# AbraSchematicVer5_SchDoc.net
KiCad netlist of a schematic drawn in Altium Designer
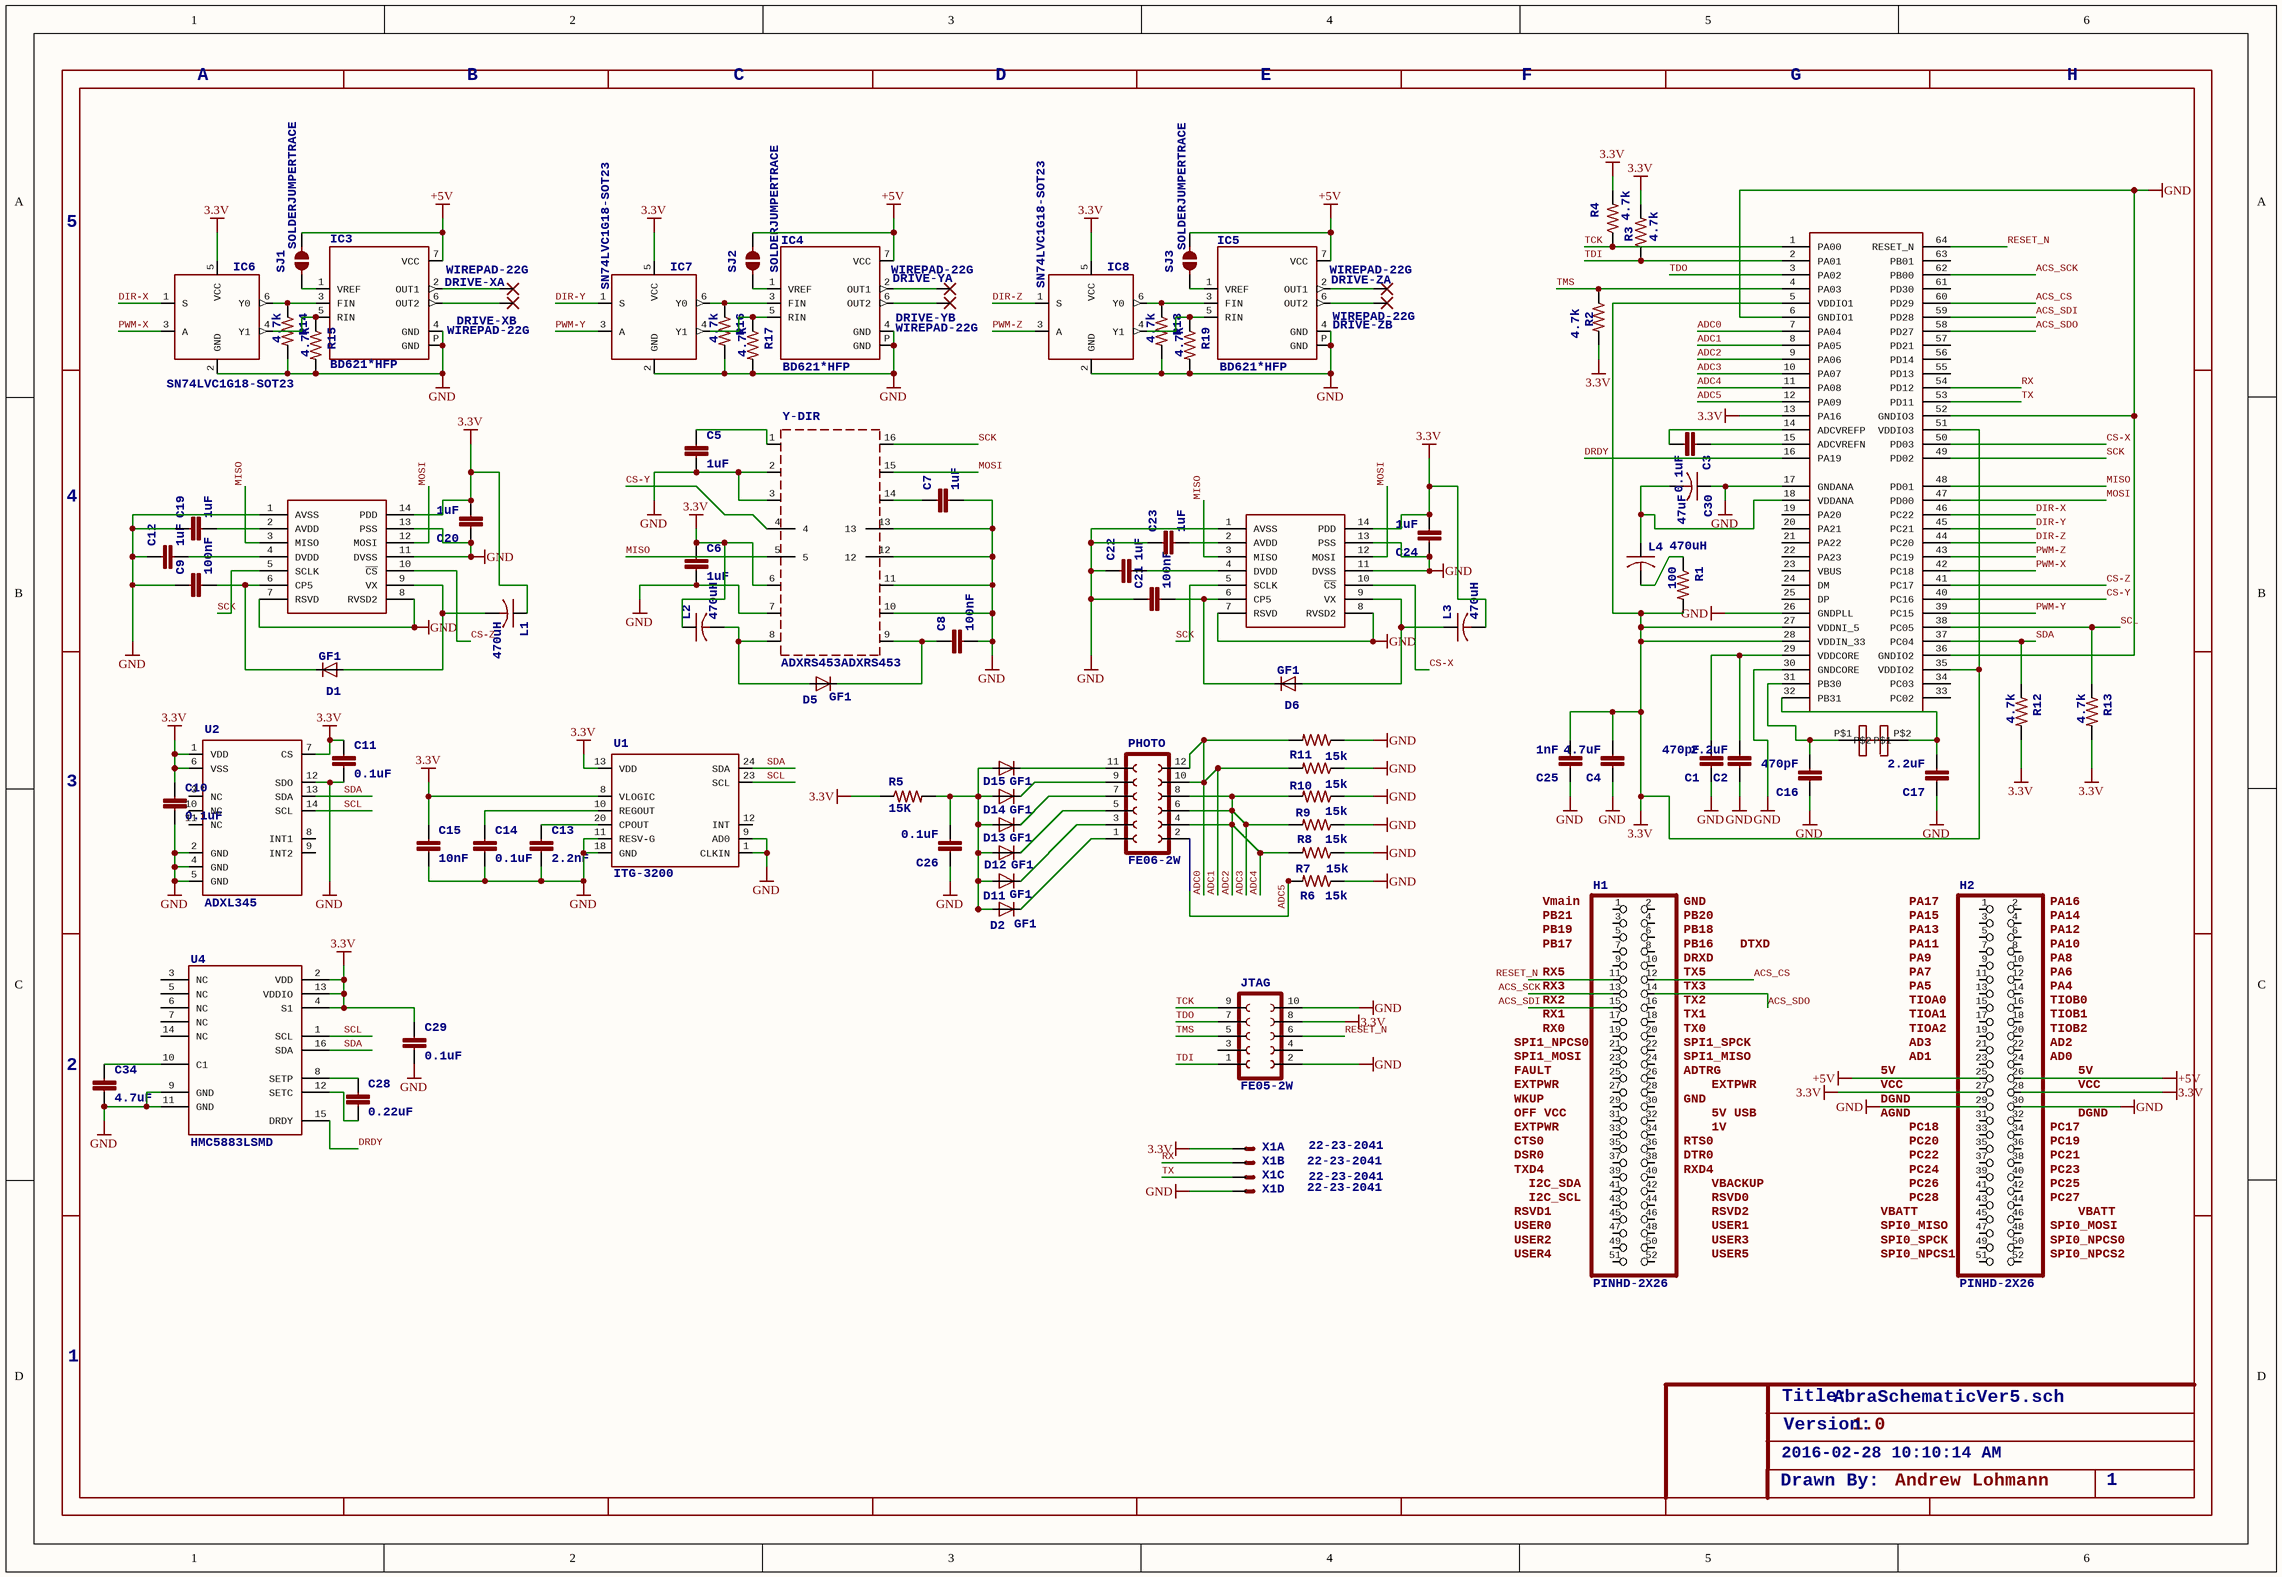
[diagram p0: AbraSchematicVer5.SchDoc.SchDoc]

(export (version "E")
  (design (tool "Eeschema 10.0.6"))
  (components
    (comp (ref "AXDRS453-LCC_X-DIR")
      (value "ADXRS453-LCC")
      (footprint "ADX-VERT")
      (libsource (lib "AndrewLib") (part "ADXRS453-LCC"))
    )
    (comp (ref "AXDRS453-LCC_Z-DIR")
      (value "ADXRS453-LCC")
      (footprint "ADX-VERT")
      (libsource (lib "AndrewLib") (part "ADXRS453-LCC"))
    )
    (comp (ref "C1")
      (value "470pF")
      (footprint "0603-CAP")
      (description "<b>Capacitor</b>\nStandard SMT, and 0.1\", and 0.2\" leaded ceramic capacitors")
      (libsource (lib "") (part "CAPACITOR-0603_2"))
    )
    (comp (ref "C2")
      (value "2.2uF")
      (footprint "0603-CAP")
      (description "<b>Capacitor</b>\nStandard SMT, and 0.1\", and 0.2\" leaded ceramic capacitors")
      (libsource (lib "") (part "CAPACITOR-0603_2"))
    )
    (comp (ref "C3")
      (value "0.1uF")
      (footprint "0603-CAP")
      (description "<b>Capacitor</b>\nStandard SMT, and 0.1\", and 0.2\" leaded ceramic capacitors")
      (libsource (lib "") (part "CAPACITOR-0603_3"))
    )
    (comp (ref "C4")
      (value "4.7uF")
      (footprint "0603-CAP")
      (description "<b>Capacitor</b>\nStandard SMT, and 0.1\", and 0.2\" leaded ceramic capacitors")
      (libsource (lib "") (part "CAPACITOR-0603_2"))
    )
    (comp (ref "C5")
      (value "1uF")
      (footprint "0603-CAP")
      (description "<b>Capacitor</b>\nStandard SMT, and 0.1\", and 0.2\" leaded ceramic capacitors")
      (libsource (lib "") (part "CAPACITOR-0603_1"))
    )
    (comp (ref "C6")
      (value "1uF")
      (footprint "0603-CAP")
      (description "<b>Capacitor</b>\nStandard SMT, and 0.1\", and 0.2\" leaded ceramic capacitors")
      (libsource (lib "") (part "CAPACITOR-0603_1"))
    )
    (comp (ref "C7")
      (value "1uF")
      (footprint "0603-CAP")
      (description "<b>Capacitor</b>\nStandard SMT, and 0.1\", and 0.2\" leaded ceramic capacitors")
      (libsource (lib "urover") (part "CAPACITOR-0603"))
    )
    (comp (ref "C8")
      (value "100nF")
      (footprint "0603-CAP")
      (description "<b>Capacitor</b>\nStandard SMT, and 0.1\", and 0.2\" leaded ceramic capacitors")
      (libsource (lib "urover") (part "CAPACITOR-0603"))
    )
    (comp (ref "C9")
      (value "100nF")
      (footprint "0603-CAP")
      (description "<b>Capacitor</b>\nStandard SMT, and 0.1\", and 0.2\" leaded ceramic capacitors")
      (libsource (lib "urover") (part "CAPACITOR-0603"))
    )
    (comp (ref "C10")
      (value "0.1uF")
      (footprint "0603-CAP")
      (description "<b>Capacitor</b>\nStandard SMT, and 0.1\", and 0.2\" leaded ceramic capacitors")
      (libsource (lib "") (part "CAPACITOR-0603_1"))
    )
    (comp (ref "C11")
      (value "0.1uF")
      (footprint "0603-CAP")
      (description "<b>Capacitor</b>\nStandard SMT, and 0.1\", and 0.2\" leaded ceramic capacitors")
      (libsource (lib "") (part "CAPACITOR-0603_1"))
    )
    (comp (ref "C12")
      (value "1uF")
      (footprint "0603-CAP")
      (description "<b>Capacitor</b>\nStandard SMT, and 0.1\", and 0.2\" leaded ceramic capacitors")
      (libsource (lib "urover") (part "CAPACITOR-0603"))
    )
    (comp (ref "C13")
      (value "2.2nF")
      (footprint "0603-CAP")
      (description "<b>Capacitor</b>\nStandard SMT, and 0.1\", and 0.2\" leaded ceramic capacitors")
      (libsource (lib "") (part "CAPACITOR-0603_1"))
    )
    (comp (ref "C14")
      (value "0.1uF")
      (footprint "0603-CAP")
      (description "<b>Capacitor</b>\nStandard SMT, and 0.1\", and 0.2\" leaded ceramic capacitors")
      (libsource (lib "") (part "CAPACITOR-0603_1"))
    )
    (comp (ref "C15")
      (value "10nF")
      (footprint "0603-CAP")
      (description "<b>Capacitor</b>\nStandard SMT, and 0.1\", and 0.2\" leaded ceramic capacitors")
      (libsource (lib "") (part "CAPACITOR-0603_1"))
    )
    (comp (ref "C16")
      (value "470pF")
      (footprint "0603-CAP")
      (description "<b>Capacitor</b>\nStandard SMT, and 0.1\", and 0.2\" leaded ceramic capacitors")
      (libsource (lib "") (part "CAPACITOR-0603_2"))
    )
    (comp (ref "C17")
      (value "2.2uF")
      (footprint "0603-CAP")
      (description "<b>Capacitor</b>\nStandard SMT, and 0.1\", and 0.2\" leaded ceramic capacitors")
      (libsource (lib "") (part "CAPACITOR-0603_2"))
    )
    (comp (ref "C19")
      (value "1uF")
      (footprint "0603-CAP")
      (description "<b>Capacitor</b>\nStandard SMT, and 0.1\", and 0.2\" leaded ceramic capacitors")
      (libsource (lib "urover") (part "CAPACITOR-0603"))
    )
    (comp (ref "C20")
      (value "1uF")
      (footprint "0603-CAP")
      (description "<b>Capacitor</b>\nStandard SMT, and 0.1\", and 0.2\" leaded ceramic capacitors")
      (libsource (lib "") (part "CAPACITOR-0603_2"))
    )
    (comp (ref "C21")
      (value "100nF")
      (footprint "0603-CAP")
      (description "<b>Capacitor</b>\nStandard SMT, and 0.1\", and 0.2\" leaded ceramic capacitors")
      (libsource (lib "urover") (part "CAPACITOR-0603"))
    )
    (comp (ref "C22")
      (value "1uF")
      (footprint "0603-CAP")
      (description "<b>Capacitor</b>\nStandard SMT, and 0.1\", and 0.2\" leaded ceramic capacitors")
      (libsource (lib "urover") (part "CAPACITOR-0603"))
    )
    (comp (ref "C23")
      (value "1uF")
      (footprint "0603-CAP")
      (description "<b>Capacitor</b>\nStandard SMT, and 0.1\", and 0.2\" leaded ceramic capacitors")
      (libsource (lib "urover") (part "CAPACITOR-0603"))
    )
    (comp (ref "C24")
      (value "1uF")
      (footprint "0603-CAP")
      (description "<b>Capacitor</b>\nStandard SMT, and 0.1\", and 0.2\" leaded ceramic capacitors")
      (libsource (lib "") (part "CAPACITOR-0603_2"))
    )
    (comp (ref "C25")
      (value "1nF")
      (footprint "0603-CAP")
      (description "<b>Capacitor</b>\nStandard SMT, and 0.1\", and 0.2\" leaded ceramic capacitors")
      (libsource (lib "") (part "CAPACITOR-0603_2"))
    )
    (comp (ref "C26")
      (value "0.1uF")
      (footprint "0603-CAP")
      (description "<b>Capacitor</b>\nStandard SMT, and 0.1\", and 0.2\" leaded ceramic capacitors")
      (libsource (lib "") (part "CAPACITOR-0603_2"))
    )
    (comp (ref "C28")
      (value "0.22uF")
      (footprint "0603-CAP")
      (description "<b>Capacitor</b>\nStandard SMT, and 0.1\", and 0.2\" leaded ceramic capacitors")
      (libsource (lib "") (part "CAPACITOR-0603_1"))
    )
    (comp (ref "C29")
      (value "0.1uF")
      (footprint "0603-CAP")
      (description "<b>Capacitor</b>\nStandard SMT, and 0.1\", and 0.2\" leaded ceramic capacitors")
      (libsource (lib "") (part "CAPACITOR-0603_1"))
    )
    (comp (ref "C30")
      (value "47uF")
      (footprint "C1210K")
      (description "<B>CAPACITOR</B>, American symbol")
      (libsource (lib "rcl") (part "C-USC1210K"))
    )
    (comp (ref "C34")
      (value "4.7uF")
      (footprint "0603-CAP")
      (description "<b>Capacitor</b>\nStandard SMT, and 0.1\", and 0.2\" leaded ceramic capacitors")
      (libsource (lib "") (part "CAPACITOR-0603_1"))
    )
    (comp (ref "CRYSTAL")
      (value "CRYSTAL-CAP")
      (footprint "CSM-3X_SMD")
      (libsource (lib "AndrewLib") (part "CRYSTAL-CAP"))
    )
    (comp (ref "D1")
      (value "GF1")
      (footprint "SMA-DO214AC")
      (description "<B>DIODE</B>")
      (libsource (lib "diode") (part "GF1"))
    )
    (comp (ref "D2")
      (value "GF1")
      (footprint "SMA-DO214AC")
      (description "<B>DIODE</B>")
      (libsource (lib "diode") (part "GF1"))
    )
    (comp (ref "D5")
      (value "GF1")
      (footprint "SMA-DO214AC")
      (description "<B>DIODE</B>")
      (libsource (lib "diode") (part "GF1"))
    )
    (comp (ref "D6")
      (value "GF1")
      (footprint "SMA-DO214AC")
      (description "<B>DIODE</B>")
      (libsource (lib "diode") (part "GF1"))
    )
    (comp (ref "D11")
      (value "GF1")
      (footprint "SMA-DO214AC")
      (description "<B>DIODE</B>")
      (libsource (lib "diode") (part "GF1"))
    )
    (comp (ref "D12")
      (value "GF1")
      (footprint "SMA-DO214AC")
      (description "<B>DIODE</B>")
      (libsource (lib "diode") (part "GF1"))
    )
    (comp (ref "D13")
      (value "GF1")
      (footprint "SMA-DO214AC")
      (description "<B>DIODE</B>")
      (libsource (lib "diode") (part "GF1"))
    )
    (comp (ref "D14")
      (value "GF1")
      (footprint "SMA-DO214AC")
      (description "<B>DIODE</B>")
      (libsource (lib "diode") (part "GF1"))
    )
    (comp (ref "D15")
      (value "GF1")
      (footprint "SMA-DO214AC")
      (description "<B>DIODE</B>")
      (libsource (lib "diode") (part "GF1"))
    )
    (comp (ref "DRIVE-XA")
      (value "WIREPAD-22G")
      (footprint "PAD-22G")
      (description "<b>THROUGH-HOLE PAD</b>")
      (libsource (lib "urover") (part "WIREPAD-22G"))
    )
    (comp (ref "DRIVE-XB")
      (value "WIREPAD-22G")
      (footprint "PAD-22G")
      (description "<b>THROUGH-HOLE PAD</b>")
      (libsource (lib "urover") (part "WIREPAD-22G"))
    )
    (comp (ref "DRIVE-YA")
      (value "WIREPAD-22G")
      (footprint "PAD-22G")
      (description "<b>THROUGH-HOLE PAD</b>")
      (libsource (lib "urover") (part "WIREPAD-22G"))
    )
    (comp (ref "DRIVE-YB")
      (value "WIREPAD-22G")
      (footprint "PAD-22G")
      (description "<b>THROUGH-HOLE PAD</b>")
      (libsource (lib "urover") (part "WIREPAD-22G"))
    )
    (comp (ref "DRIVE-ZA")
      (value "WIREPAD-22G")
      (footprint "PAD-22G")
      (description "<b>THROUGH-HOLE PAD</b>")
      (libsource (lib "urover") (part "WIREPAD-22G"))
    )
    (comp (ref "DRIVE-ZB")
      (value "WIREPAD-22G")
      (footprint "PAD-22G")
      (description "<b>THROUGH-HOLE PAD</b>")
      (libsource (lib "urover") (part "WIREPAD-22G"))
    )
    (comp (ref "H1")
      (value "PINHD-2X26")
      (footprint "HEADER-2X26")
      (description "<b>PIN HEADER</b>")
      (libsource (lib "urover") (part "PINHD-2X26"))
    )
    (comp (ref "H2")
      (value "PINHD-2X26")
      (footprint "HEADER-2X26")
      (description "<b>PIN HEADER</b>")
      (libsource (lib "urover") (part "PINHD-2X26"))
    )
    (comp (ref "IC3")
      (value "BD621*HFP")
      (footprint "HRP7")
      (fields (field (name "MPN") "BD6232HFP-TR"))
      (libsource (lib "urover") (part "BD621*HFP"))
    )
    (comp (ref "IC4")
      (value "BD621*HFP")
      (footprint "HRP7")
      (fields (field (name "MPN") "BD6232HFP-TR"))
      (libsource (lib "urover") (part "BD621*HFP"))
    )
    (comp (ref "IC5")
      (value "BD621*HFP")
      (footprint "HRP7")
      (fields (field (name "MPN") "BD6232HFP-TR"))
      (libsource (lib "urover") (part "BD621*HFP"))
    )
    (comp (ref "IC6")
      (value "SN74LVC1G18-SOT23")
      (footprint "SOT23-6")
      (libsource (lib "urover") (part "SN74LVC1G18-SOT23"))
    )
    (comp (ref "IC7")
      (value "SN74LVC1G18-SOT23")
      (footprint "SOT23-6")
      (libsource (lib "urover") (part "SN74LVC1G18-SOT23"))
    )
    (comp (ref "IC8")
      (value "SN74LVC1G18-SOT23")
      (footprint "SOT23-6")
      (libsource (lib "urover") (part "SN74LVC1G18-SOT23"))
    )
    (comp (ref "JTAG")
      (value "FE05-2W")
      (footprint "FE05-2W")
      (description "<b>FEMALE HEADER</b>")
      (libsource (lib "AndrewLib") (part "FE05-2W"))
    )
    (comp (ref "L1")
      (value "470uH")
      (footprint "C1210K")
      (description "<B>CAPACITOR</B>, American symbol")
      (libsource (lib "rcl") (part "C-USC1210K"))
    )
    (comp (ref "L2")
      (value "470uH")
      (footprint "C1210K")
      (description "<B>CAPACITOR</B>, American symbol")
      (libsource (lib "rcl") (part "C-USC1210K"))
    )
    (comp (ref "L3")
      (value "470uH")
      (footprint "C1210K")
      (description "<B>CAPACITOR</B>, American symbol")
      (libsource (lib "rcl") (part "C-USC1210K"))
    )
    (comp (ref "L4")
      (value "470uH")
      (footprint "C1210K")
      (description "<B>CAPACITOR</B>, American symbol")
      (libsource (lib "rcl") (part "C-USC1210K"))
    )
    (comp (ref "PHOTO")
      (value "FE06-2W")
      (footprint "FE06-2W")
      (description "<b>FEMALE HEADER</b>")
      (libsource (lib "AndrewLib") (part "FE06-2W"))
    )
    (comp (ref "R1")
      (value "100")
      (footprint "0603-RES")
      (description "<p><b>Resistor</b></p>\nBasic schematic elements and footprints for resistors.")
      (libsource (lib "urover") (part "RESISTOR-0603"))
    )
    (comp (ref "R2")
      (value "4.7k")
      (footprint "0603-RES")
      (description "<p><b>Resistor</b></p>\nBasic schematic elements and footprints for resistors.")
      (libsource (lib "urover") (part "RESISTOR-0603"))
    )
    (comp (ref "R3")
      (value "4.7k")
      (footprint "0603-RES")
      (description "<p><b>Resistor</b></p>\nBasic schematic elements and footprints for resistors.")
      (libsource (lib "urover") (part "RESISTOR-0603"))
    )
    (comp (ref "R4")
      (value "4.7k")
      (footprint "0603-RES")
      (description "<p><b>Resistor</b></p>\nBasic schematic elements and footprints for resistors.")
      (libsource (lib "urover") (part "RESISTOR-0603"))
    )
    (comp (ref "R5")
      (value "15K")
      (footprint "0603-RES")
      (description "<p><b>Resistor</b></p>\nBasic schematic elements and footprints for resistors.")
      (libsource (lib "urover") (part "RESISTOR-0603"))
    )
    (comp (ref "R6")
      (value "15k")
      (footprint "0603-RES")
      (description "<p><b>Resistor</b></p>\nBasic schematic elements and footprints for resistors.")
      (libsource (lib "urover") (part "RESISTOR-0603"))
    )
    (comp (ref "R7")
      (value "15k")
      (footprint "0603-RES")
      (description "<p><b>Resistor</b></p>\nBasic schematic elements and footprints for resistors.")
      (libsource (lib "urover") (part "RESISTOR-0603"))
    )
    (comp (ref "R8")
      (value "15k")
      (footprint "0603-RES")
      (description "<p><b>Resistor</b></p>\nBasic schematic elements and footprints for resistors.")
      (libsource (lib "urover") (part "RESISTOR-0603"))
    )
    (comp (ref "R9")
      (value "15k")
      (footprint "0603-RES")
      (description "<p><b>Resistor</b></p>\nBasic schematic elements and footprints for resistors.")
      (libsource (lib "urover") (part "RESISTOR-0603"))
    )
    (comp (ref "R10")
      (value "15k")
      (footprint "0603-RES")
      (description "<p><b>Resistor</b></p>\nBasic schematic elements and footprints for resistors.")
      (libsource (lib "urover") (part "RESISTOR-0603"))
    )
    (comp (ref "R11")
      (value "15k")
      (footprint "0603-RES")
      (description "<p><b>Resistor</b></p>\nBasic schematic elements and footprints for resistors.")
      (libsource (lib "urover") (part "RESISTOR-0603"))
    )
    (comp (ref "R12")
      (value "4.7k")
      (footprint "0603-RES")
      (description "<p><b>Resistor</b></p>\nBasic schematic elements and footprints for resistors.")
      (libsource (lib "urover") (part "RESISTOR-0603"))
    )
    (comp (ref "R13")
      (value "4.7k")
      (footprint "0603-RES")
      (description "<p><b>Resistor</b></p>\nBasic schematic elements and footprints for resistors.")
      (libsource (lib "urover") (part "RESISTOR-0603"))
    )
    (comp (ref "R14")
      (value "4.7k")
      (footprint "0603-RES")
      (description "<p><b>Resistor</b></p>\nBasic schematic elements and footprints for resistors.")
      (libsource (lib "urover") (part "RESISTOR-0603"))
    )
    (comp (ref "R15")
      (value "4.7k")
      (footprint "0603-RES")
      (description "<p><b>Resistor</b></p>\nBasic schematic elements and footprints for resistors.")
      (libsource (lib "urover") (part "RESISTOR-0603"))
    )
    (comp (ref "R16")
      (value "4.7k")
      (footprint "0603-RES")
      (description "<p><b>Resistor</b></p>\nBasic schematic elements and footprints for resistors.")
      (libsource (lib "urover") (part "RESISTOR-0603"))
    )
    (comp (ref "R17")
      (value "4.7k")
      (footprint "0603-RES")
      (description "<p><b>Resistor</b></p>\nBasic schematic elements and footprints for resistors.")
      (libsource (lib "urover") (part "RESISTOR-0603"))
    )
    (comp (ref "R18")
      (value "4.7k")
      (footprint "0603-RES")
      (description "<p><b>Resistor</b></p>\nBasic schematic elements and footprints for resistors.")
      (libsource (lib "urover") (part "RESISTOR-0603"))
    )
    (comp (ref "R19")
      (value "4.7k")
      (footprint "0603-RES")
      (description "<p><b>Resistor</b></p>\nBasic schematic elements and footprints for resistors.")
      (libsource (lib "urover") (part "RESISTOR-0603"))
    )
    (comp (ref "SJ1")
      (value "SOLDERJUMPERTRACE")
      (footprint "SJ_2S-TRACE")
      (libsource (lib "SparkFun") (part "SOLDERJUMPERTRACE"))
    )
    (comp (ref "SJ2")
      (value "SOLDERJUMPERTRACE")
      (footprint "SJ_2S-TRACE")
      (libsource (lib "SparkFun") (part "SOLDERJUMPERTRACE"))
    )
    (comp (ref "SJ3")
      (value "SOLDERJUMPERTRACE")
      (footprint "SJ_2S-TRACE")
      (libsource (lib "SparkFun") (part "SOLDERJUMPERTRACE"))
    )
    (comp (ref "U$1")
      (value "AT32UC3C-LEAD2")
      (footprint "TQFP64-CORRECT")
      (libsource (lib "AndrewLib") (part "AT32UC3C-LEAD2"))
    )
    (comp (ref "U1")
      (value "ITG-3200")
      (footprint "QFN-24")
      (description "ITG-3200 3-axis gyro, digital output, qfn24 package")
      (libsource (lib "urover") (part "ITG-3200"))
    )
    (comp (ref "U2") (value "ADXL345") (footprint "LGA14") (libsource (lib "urover") (part "ADXL345")))
    (comp (ref "U4")
      (value "HMC5883LSMD")
      (footprint "16LPCC")
      (description "3 Axis Digital Compass IC")
      (libsource (lib "urover") (part "HMC5883LSMD"))
    )
    (comp (ref "X1")
      (value "22-23-2041")
      (footprint "22-23-2041")
      (description ".100\" (2.54mm) Center Header - 4 Pin")
      (fields (field (name "MF") "MOLEX"))
      (libsource (lib "con-molex") (part "22-23-2041"))
    )
    (comp (ref "Y-DIR")
      (value "ADXRS453ADXRS453")
      (footprint "N5")
      (description "Angular Rate Sensor.")
      (libsource (lib "AndrewLib") (part "ADXRS453ADXRS453"))
    )
  )
  (nets
    (net (code "1") (name "+5V") (class "Default")
      (node (ref "H2") (pin "25") (pinfunction "25_25") (pintype "passive"))
      (node (ref "H2") (pin "26") (pinfunction "26_26") (pintype "passive"))
      (node (ref "IC3") (pin "7") (pinfunction "VCC_7") (pintype "power_in"))
      (node (ref "IC4") (pin "7") (pinfunction "VCC_7") (pintype "power_in"))
      (node (ref "IC5") (pin "7") (pinfunction "VCC_7") (pintype "power_in"))
      (node (ref "SJ1") (pin "2") (pinfunction "2_2") (pintype "passive"))
      (node (ref "SJ2") (pin "2") (pinfunction "2_2") (pintype "passive"))
      (node (ref "SJ3") (pin "2") (pinfunction "2_2") (pintype "passive"))
    )
    (net (code "2") (name "/ACS_CS") (class "Default")
      (node (ref "H1") (pin "12") (pinfunction "12_12") (pintype "passive"))
      (node (ref "U$1") (pin "60") (pinfunction "PD29_60") (pintype "passive"))
    )
    (net (code "3") (name "/ACS_SCK") (class "Default")
      (node (ref "U$1") (pin "62") (pinfunction "PB00_62") (pintype "passive"))
    )
    (net (code "4") (name "/ACS_SDI") (class "Default")
      (node (ref "U$1") (pin "59") (pinfunction "PD28_59") (pintype "passive"))
    )
    (net (code "5") (name "/ACS_SDO") (class "Default")
      (node (ref "H1") (pin "14") (pinfunction "14_14") (pintype "passive"))
      (node (ref "U$1") (pin "58") (pinfunction "PD27_58") (pintype "passive"))
    )
    (net (code "6") (name "/ADC0") (class "Default")
      (node (ref "PHOTO") (pin "10") (pinfunction "10_10") (pintype "passive"))
      (node (ref "PHOTO") (pin "12") (pinfunction "12_12") (pintype "passive"))
      (node (ref "R10") (pin "2") (pinfunction "2_2") (pintype "passive"))
      (node (ref "R11") (pin "2") (pinfunction "2_2") (pintype "passive"))
      (node (ref "U$1") (pin "7") (pinfunction "PA04_7") (pintype "passive"))
      (node (ref "U$1") (pin "8") (pinfunction "PA05_8") (pintype "passive"))
    )
    (net (code "7") (name "/ADC2") (class "Default")
      (node (ref "PHOTO") (pin "4") (pinfunction "4_4") (pintype "passive"))
      (node (ref "PHOTO") (pin "6") (pinfunction "6_6") (pintype "passive"))
      (node (ref "PHOTO") (pin "8") (pinfunction "8_8") (pintype "passive"))
      (node (ref "R7") (pin "2") (pinfunction "2_2") (pintype "passive"))
      (node (ref "R8") (pin "2") (pinfunction "2_2") (pintype "passive"))
      (node (ref "R9") (pin "2") (pinfunction "2_2") (pintype "passive"))
      (node (ref "U$1") (pin "10") (pinfunction "PA07_10") (pintype "passive"))
      (node (ref "U$1") (pin "11") (pinfunction "PA08_11") (pintype "passive"))
      (node (ref "U$1") (pin "9") (pinfunction "PA06_9") (pintype "passive"))
    )
    (net (code "8") (name "/ADC5") (class "Default")
      (node (ref "PHOTO") (pin "2") (pinfunction "2_2") (pintype "passive"))
      (node (ref "R6") (pin "2") (pinfunction "2_2") (pintype "passive"))
      (node (ref "U$1") (pin "12") (pinfunction "PA09_12") (pintype "passive"))
    )
    (net (code "9") (name "/CS-X") (class "Default")
      (node (ref "AXDRS453-LCC_X-DIR") (pin "10") (pinfunction "~{CS}_10") (pintype "passive"))
      (node (ref "U$1") (pin "50") (pinfunction "PD03_50") (pintype "passive"))
    )
    (net (code "10") (name "/CS-Y") (class "Default")
      (node (ref "U$1") (pin "40") (pinfunction "PC16_40") (pintype "passive"))
      (node (ref "Y-DIR") (pin "4") (pinfunction "4_4") (pintype "passive"))
    )
    (net (code "11") (name "/CS-Z") (class "Default")
      (node (ref "AXDRS453-LCC_Z-DIR") (pin "10") (pinfunction "~{CS}_10") (pintype "passive"))
      (node (ref "U$1") (pin "41") (pinfunction "PC17_41") (pintype "passive"))
    )
    (net (code "12") (name "/DIR-X") (class "Default")
      (node (ref "IC6") (pin "1") (pinfunction "S_1") (pintype "passive"))
      (node (ref "U$1") (pin "46") (pinfunction "PC22_46") (pintype "passive"))
    )
    (net (code "13") (name "/DIR-Y") (class "Default")
      (node (ref "IC7") (pin "1") (pinfunction "S_1") (pintype "passive"))
      (node (ref "U$1") (pin "45") (pinfunction "PC21_45") (pintype "passive"))
    )
    (net (code "14") (name "/DIR-Z") (class "Default")
      (node (ref "IC8") (pin "1") (pinfunction "S_1") (pintype "passive"))
      (node (ref "U$1") (pin "44") (pinfunction "PC20_44") (pintype "passive"))
    )
    (net (code "15") (name "/DRDY") (class "Default")
      (node (ref "U$1") (pin "16") (pinfunction "PA19_16") (pintype "passive"))
      (node (ref "U4") (pin "15") (pinfunction "DRDY_15") (pintype "passive"))
    )
    (net (code "16") (name "/MISO") (class "Default")
      (node (ref "AXDRS453-LCC_X-DIR") (pin "3") (pinfunction "MISO_3") (pintype "passive"))
      (node (ref "AXDRS453-LCC_Z-DIR") (pin "3") (pinfunction "MISO_3") (pintype "passive"))
      (node (ref "U$1") (pin "48") (pinfunction "PD01_48") (pintype "passive"))
      (node (ref "Y-DIR") (pin "5") (pinfunction "5_5") (pintype "passive"))
    )
    (net (code "17") (name "/MOSI") (class "Default")
      (node (ref "AXDRS453-LCC_X-DIR") (pin "12") (pinfunction "MOSI_12") (pintype "passive"))
      (node (ref "AXDRS453-LCC_Z-DIR") (pin "12") (pinfunction "MOSI_12") (pintype "passive"))
      (node (ref "U$1") (pin "47") (pinfunction "PD00_47") (pintype "passive"))
      (node (ref "Y-DIR") (pin "15") (pinfunction "15_15") (pintype "passive"))
    )
    (net (code "18") (name "/PWM-X") (class "Default")
      (node (ref "IC6") (pin "3") (pinfunction "A_3") (pintype "passive"))
      (node (ref "U$1") (pin "42") (pinfunction "PC18_42") (pintype "passive"))
    )
    (net (code "19") (name "/PWM-Y") (class "Default")
      (node (ref "IC7") (pin "3") (pinfunction "A_3") (pintype "passive"))
      (node (ref "U$1") (pin "39") (pinfunction "PC15_39") (pintype "passive"))
    )
    (net (code "20") (name "/PWM-Z") (class "Default")
      (node (ref "IC8") (pin "3") (pinfunction "A_3") (pintype "passive"))
      (node (ref "U$1") (pin "43") (pinfunction "PC19_43") (pintype "passive"))
    )
    (net (code "21") (name "/RESET_N") (class "Default")
      (node (ref "JTAG") (pin "6") (pinfunction "6_6") (pintype "passive"))
      (node (ref "U$1") (pin "64") (pinfunction "RESET_N_64") (pintype "passive"))
    )
    (net (code "22") (name "/RX") (class "Default")
      (node (ref "U$1") (pin "54") (pinfunction "PD12_54") (pintype "passive"))
      (node (ref "X1") (pin "2") (pinfunction "S_2") (pintype "passive"))
    )
    (net (code "23") (name "/SCK") (class "Default")
      (node (ref "AXDRS453-LCC_X-DIR") (pin "5") (pinfunction "SCLK_5") (pintype "passive"))
      (node (ref "AXDRS453-LCC_Z-DIR") (pin "5") (pinfunction "SCLK_5") (pintype "passive"))
      (node (ref "U$1") (pin "49") (pinfunction "PD02_49") (pintype "passive"))
      (node (ref "Y-DIR") (pin "16") (pinfunction "16_16") (pintype "passive"))
    )
    (net (code "24") (name "/SCL") (class "Default")
      (node (ref "R13") (pin "1") (pinfunction "1_1") (pintype "passive"))
      (node (ref "U$1") (pin "38") (pinfunction "PC05_38") (pintype "passive"))
      (node (ref "U1") (pin "23") (pinfunction "SCL_23") (pintype "passive"))
      (node (ref "U2") (pin "14") (pinfunction "SCL_14") (pintype "passive"))
      (node (ref "U4") (pin "1") (pinfunction "SCL_1") (pintype "passive"))
    )
    (net (code "25") (name "/SDA") (class "Default")
      (node (ref "R12") (pin "1") (pinfunction "1_1") (pintype "passive"))
      (node (ref "U$1") (pin "37") (pinfunction "PC04_37") (pintype "passive"))
      (node (ref "U1") (pin "24") (pinfunction "SDA_24") (pintype "passive"))
      (node (ref "U2") (pin "13") (pinfunction "SDA_13") (pintype "passive"))
      (node (ref "U4") (pin "16") (pinfunction "SDA_16") (pintype "passive"))
    )
    (net (code "26") (name "/TCK") (class "Default")
      (node (ref "JTAG") (pin "9") (pinfunction "9_9") (pintype "passive"))
      (node (ref "R4") (pin "1") (pinfunction "1_1") (pintype "passive"))
      (node (ref "U$1") (pin "1") (pinfunction "PA00_1") (pintype "passive"))
    )
    (net (code "27") (name "/TDI") (class "Default")
      (node (ref "JTAG") (pin "1") (pinfunction "1_1") (pintype "passive"))
      (node (ref "R3") (pin "1") (pinfunction "1_1") (pintype "passive"))
      (node (ref "U$1") (pin "2") (pinfunction "PA01_2") (pintype "passive"))
    )
    (net (code "28") (name "/TDO") (class "Default")
      (node (ref "JTAG") (pin "7") (pinfunction "7_7") (pintype "passive"))
      (node (ref "U$1") (pin "3") (pinfunction "PA02_3") (pintype "passive"))
    )
    (net (code "29") (name "/TMS") (class "Default")
      (node (ref "JTAG") (pin "5") (pinfunction "5_5") (pintype "passive"))
      (node (ref "R2") (pin "1") (pinfunction "1_1") (pintype "passive"))
      (node (ref "U$1") (pin "4") (pinfunction "PA03_4") (pintype "passive"))
    )
    (net (code "30") (name "/TX") (class "Default")
      (node (ref "U$1") (pin "53") (pinfunction "PD11_53") (pintype "passive"))
      (node (ref "X1") (pin "3") (pinfunction "S_3") (pintype "passive"))
    )
    (net (code "31") (name "3.3V") (class "Default")
      (node (ref "AXDRS453-LCC_X-DIR") (pin "14") (pinfunction "PDD_14") (pintype "passive"))
      (node (ref "AXDRS453-LCC_Z-DIR") (pin "14") (pinfunction "PDD_14") (pintype "passive"))
      (node (ref "C10") (pin "1") (pinfunction "1_1") (pintype "passive"))
      (node (ref "C11") (pin "1") (pinfunction "1_1") (pintype "passive"))
      (node (ref "C15") (pin "1") (pinfunction "1_1") (pintype "passive"))
      (node (ref "C20") (pin "2") (pinfunction "2_2") (pintype "passive"))
      (node (ref "C24") (pin "2") (pinfunction "2_2") (pintype "passive"))
      (node (ref "C25") (pin "2") (pinfunction "2_2") (pintype "passive"))
      (node (ref "C29") (pin "1") (pinfunction "1_1") (pintype "passive"))
      (node (ref "C4") (pin "2") (pinfunction "2_2") (pintype "passive"))
      (node (ref "C6") (pin "1") (pinfunction "1_1") (pintype "passive"))
      (node (ref "H2") (pin "27") (pinfunction "27_27") (pintype "passive"))
      (node (ref "H2") (pin "28") (pinfunction "28_28") (pintype "passive"))
      (node (ref "IC6") (pin "5") (pinfunction "VCC_5") (pintype "power_in"))
      (node (ref "IC7") (pin "5") (pinfunction "VCC_5") (pintype "power_in"))
      (node (ref "IC8") (pin "5") (pinfunction "VCC_5") (pintype "power_in"))
      (node (ref "JTAG") (pin "8") (pinfunction "8_8") (pintype "passive"))
      (node (ref "L1") (pin "1") (pinfunction "1_1") (pintype "passive"))
      (node (ref "L2") (pin "1") (pinfunction "1_1") (pintype "passive"))
      (node (ref "L3") (pin "2") (pinfunction "2_2") (pintype "passive"))
      (node (ref "R1") (pin "2") (pinfunction "2_2") (pintype "passive"))
      (node (ref "R12") (pin "2") (pinfunction "2_2") (pintype "passive"))
      (node (ref "R13") (pin "2") (pinfunction "2_2") (pintype "passive"))
      (node (ref "R2") (pin "2") (pinfunction "2_2") (pintype "passive"))
      (node (ref "R3") (pin "2") (pinfunction "2_2") (pintype "passive"))
      (node (ref "R4") (pin "2") (pinfunction "2_2") (pintype "passive"))
      (node (ref "R5") (pin "1") (pinfunction "1_1") (pintype "passive"))
      (node (ref "U$1") (pin "13") (pinfunction "PA16_13") (pintype "passive"))
      (node (ref "U$1") (pin "27") (pinfunction "VDDNI_5_27") (pintype "passive"))
      (node (ref "U$1") (pin "28") (pinfunction "VDDIN_33_28") (pintype "passive"))
      (node (ref "U$1") (pin "35") (pinfunction "VDDIO2_35") (pintype "passive"))
      (node (ref "U$1") (pin "5") (pinfunction "VDDIO1_5") (pintype "passive"))
      (node (ref "U$1") (pin "51") (pinfunction "VDDIO3_51") (pintype "passive"))
      (node (ref "U1") (pin "13") (pinfunction "VDD_13") (pintype "passive"))
      (node (ref "U1") (pin "8") (pinfunction "VLOGIC_8") (pintype "passive"))
      (node (ref "U2") (pin "1") (pinfunction "VDD_1") (pintype "passive"))
      (node (ref "U2") (pin "6") (pinfunction "VSS_6") (pintype "passive"))
      (node (ref "U2") (pin "7") (pinfunction "CS_7") (pintype "passive"))
      (node (ref "U4") (pin "13") (pinfunction "VDDIO_13") (pintype "passive"))
      (node (ref "U4") (pin "2") (pinfunction "VDD_2") (pintype "passive"))
      (node (ref "U4") (pin "4") (pinfunction "S1_4") (pintype "passive"))
      (node (ref "X1") (pin "1") (pinfunction "S_1") (pintype "passive"))
      (node (ref "Y-DIR") (pin "6") (pinfunction "6_6") (pintype "passive"))
    )
    (net (code "32") (name "GND") (class "Default")
      (node (ref "AXDRS453-LCC_X-DIR") (pin "1") (pinfunction "AVSS_1") (pintype "passive"))
      (node (ref "AXDRS453-LCC_X-DIR") (pin "11") (pinfunction "DVSS_11") (pintype "passive"))
      (node (ref "AXDRS453-LCC_X-DIR") (pin "13") (pinfunction "PSS_13") (pintype "passive"))
      (node (ref "AXDRS453-LCC_X-DIR") (pin "7") (pinfunction "RSVD_7") (pintype "passive"))
      (node (ref "AXDRS453-LCC_X-DIR") (pin "8") (pinfunction "RVSD2_8") (pintype "passive"))
      (node (ref "AXDRS453-LCC_Z-DIR") (pin "1") (pinfunction "AVSS_1") (pintype "passive"))
      (node (ref "AXDRS453-LCC_Z-DIR") (pin "11") (pinfunction "DVSS_11") (pintype "passive"))
      (node (ref "AXDRS453-LCC_Z-DIR") (pin "13") (pinfunction "PSS_13") (pintype "passive"))
      (node (ref "AXDRS453-LCC_Z-DIR") (pin "7") (pinfunction "RSVD_7") (pintype "passive"))
      (node (ref "AXDRS453-LCC_Z-DIR") (pin "8") (pinfunction "RVSD2_8") (pintype "passive"))
      (node (ref "C1") (pin "1") (pinfunction "1_1") (pintype "passive"))
      (node (ref "C10") (pin "2") (pinfunction "2_2") (pintype "passive"))
      (node (ref "C11") (pin "2") (pinfunction "2_2") (pintype "passive"))
      (node (ref "C12") (pin "1") (pinfunction "1_1") (pintype "passive"))
      (node (ref "C13") (pin "2") (pinfunction "2_2") (pintype "passive"))
      (node (ref "C14") (pin "2") (pinfunction "2_2") (pintype "passive"))
      (node (ref "C15") (pin "2") (pinfunction "2_2") (pintype "passive"))
      (node (ref "C16") (pin "1") (pinfunction "1_1") (pintype "passive"))
      (node (ref "C17") (pin "1") (pinfunction "1_1") (pintype "passive"))
      (node (ref "C19") (pin "1") (pinfunction "1_1") (pintype "passive"))
      (node (ref "C2") (pin "1") (pinfunction "1_1") (pintype "passive"))
      (node (ref "C20") (pin "1") (pinfunction "1_1") (pintype "passive"))
      (node (ref "C21") (pin "1") (pinfunction "1_1") (pintype "passive"))
      (node (ref "C22") (pin "1") (pinfunction "1_1") (pintype "passive"))
      (node (ref "C23") (pin "1") (pinfunction "1_1") (pintype "passive"))
      (node (ref "C24") (pin "1") (pinfunction "1_1") (pintype "passive"))
      (node (ref "C25") (pin "1") (pinfunction "1_1") (pintype "passive"))
      (node (ref "C26") (pin "1") (pinfunction "1_1") (pintype "passive"))
      (node (ref "C29") (pin "2") (pinfunction "2_2") (pintype "passive"))
      (node (ref "C30") (pin "1") (pinfunction "1_1") (pintype "passive"))
      (node (ref "C34") (pin "2") (pinfunction "2_2") (pintype "passive"))
      (node (ref "C4") (pin "1") (pinfunction "1_1") (pintype "passive"))
      (node (ref "C5") (pin "2") (pinfunction "2_2") (pintype "passive"))
      (node (ref "C6") (pin "2") (pinfunction "2_2") (pintype "passive"))
      (node (ref "C7") (pin "2") (pinfunction "2_2") (pintype "passive"))
      (node (ref "C8") (pin "2") (pinfunction "2_2") (pintype "passive"))
      (node (ref "C9") (pin "1") (pinfunction "1_1") (pintype "passive"))
      (node (ref "H2") (pin "29") (pinfunction "29_29") (pintype "passive"))
      (node (ref "H2") (pin "30") (pinfunction "30_30") (pintype "passive"))
      (node (ref "IC3") (pin "4") (pinfunction "GND_4") (pintype "power_in"))
      (node (ref "IC3") (pin "P") (pinfunction "GND_P") (pintype "power_in"))
      (node (ref "IC4") (pin "4") (pinfunction "GND_4") (pintype "power_in"))
      (node (ref "IC4") (pin "P") (pinfunction "GND_P") (pintype "power_in"))
      (node (ref "IC5") (pin "4") (pinfunction "GND_4") (pintype "power_in"))
      (node (ref "IC5") (pin "P") (pinfunction "GND_P") (pintype "power_in"))
      (node (ref "IC6") (pin "2") (pinfunction "GND_2") (pintype "power_in"))
      (node (ref "IC7") (pin "2") (pinfunction "GND_2") (pintype "power_in"))
      (node (ref "IC8") (pin "2") (pinfunction "GND_2") (pintype "power_in"))
      (node (ref "JTAG") (pin "10") (pinfunction "10_10") (pintype "passive"))
      (node (ref "JTAG") (pin "2") (pinfunction "2_2") (pintype "passive"))
      (node (ref "R10") (pin "1") (pinfunction "1_1") (pintype "passive"))
      (node (ref "R11") (pin "1") (pinfunction "1_1") (pintype "passive"))
      (node (ref "R14") (pin "2") (pinfunction "2_2") (pintype "passive"))
      (node (ref "R15") (pin "2") (pinfunction "2_2") (pintype "passive"))
      (node (ref "R16") (pin "2") (pinfunction "2_2") (pintype "passive"))
      (node (ref "R17") (pin "2") (pinfunction "2_2") (pintype "passive"))
      (node (ref "R18") (pin "2") (pinfunction "2_2") (pintype "passive"))
      (node (ref "R19") (pin "2") (pinfunction "2_2") (pintype "passive"))
      (node (ref "R6") (pin "1") (pinfunction "1_1") (pintype "passive"))
      (node (ref "R7") (pin "1") (pinfunction "1_1") (pintype "passive"))
      (node (ref "R8") (pin "1") (pinfunction "1_1") (pintype "passive"))
      (node (ref "R9") (pin "1") (pinfunction "1_1") (pintype "passive"))
      (node (ref "U$1") (pin "17") (pinfunction "GNDANA_17") (pintype "passive"))
      (node (ref "U$1") (pin "26") (pinfunction "GNDPLL_26") (pintype "passive"))
      (node (ref "U$1") (pin "30") (pinfunction "GNDCORE_30") (pintype "passive"))
      (node (ref "U$1") (pin "36") (pinfunction "GNDIO2_36") (pintype "passive"))
      (node (ref "U$1") (pin "52") (pinfunction "GNDIO3_52") (pintype "passive"))
      (node (ref "U$1") (pin "6") (pinfunction "GNDIO1_6") (pintype "passive"))
      (node (ref "U1") (pin "1") (pinfunction "CLKIN_1") (pintype "passive"))
      (node (ref "U1") (pin "11") (pinfunction "RESV-G_11") (pintype "passive"))
      (node (ref "U1") (pin "18") (pinfunction "GND_18") (pintype "passive"))
      (node (ref "U1") (pin "9") (pinfunction "AD0_9") (pintype "passive"))
      (node (ref "U2") (pin "12") (pinfunction "SDO_12") (pintype "passive"))
      (node (ref "U2") (pin "2") (pinfunction "GND_2") (pintype "passive"))
      (node (ref "U2") (pin "4") (pinfunction "GND_4") (pintype "passive"))
      (node (ref "U2") (pin "5") (pinfunction "GND_5") (pintype "passive"))
      (node (ref "U4") (pin "11") (pinfunction "GND_11") (pintype "passive"))
      (node (ref "U4") (pin "9") (pinfunction "GND_9") (pintype "passive"))
      (node (ref "X1") (pin "4") (pinfunction "S_4") (pintype "passive"))
      (node (ref "Y-DIR") (pin "10") (pinfunction "10_10") (pintype "passive"))
      (node (ref "Y-DIR") (pin "11") (pinfunction "11_11") (pintype "passive"))
      (node (ref "Y-DIR") (pin "12") (pinfunction "12_12") (pintype "passive"))
      (node (ref "Y-DIR") (pin "13") (pinfunction "13_13") (pintype "passive"))
      (node (ref "Y-DIR") (pin "2") (pinfunction "2_2") (pintype "passive"))
      (node (ref "Y-DIR") (pin "3") (pinfunction "3_3") (pintype "passive"))
      (node (ref "Y-DIR") (pin "7") (pinfunction "7_7") (pintype "passive"))
    )
    (net (code "33") (name "Net-(AXDRS453-LCC_X-DIR-AVDD)") (class "Default")
      (node (ref "AXDRS453-LCC_X-DIR") (pin "2") (pinfunction "AVDD_2") (pintype "passive"))
      (node (ref "C23") (pin "2") (pinfunction "2_2") (pintype "passive"))
    )
    (net (code "34") (name "Net-(AXDRS453-LCC_X-DIR-CP5)") (class "Default")
      (node (ref "AXDRS453-LCC_X-DIR") (pin "6") (pinfunction "CP5_6") (pintype "passive"))
      (node (ref "C21") (pin "2") (pinfunction "2_2") (pintype "passive"))
      (node (ref "D6") (pin "K") (pinfunction "C_K") (pintype "passive"))
    )
    (net (code "35") (name "Net-(AXDRS453-LCC_X-DIR-DVDD)") (class "Default")
      (node (ref "AXDRS453-LCC_X-DIR") (pin "4") (pinfunction "DVDD_4") (pintype "passive"))
      (node (ref "C22") (pin "2") (pinfunction "2_2") (pintype "passive"))
    )
    (net (code "36") (name "Net-(AXDRS453-LCC_X-DIR-VX)") (class "Default")
      (node (ref "AXDRS453-LCC_X-DIR") (pin "9") (pinfunction "VX_9") (pintype "passive"))
      (node (ref "D6") (pin "A") (pinfunction "A_A") (pintype "passive"))
      (node (ref "L3") (pin "1") (pinfunction "1_1") (pintype "passive"))
    )
    (net (code "37") (name "Net-(AXDRS453-LCC_Z-DIR-AVDD)") (class "Default")
      (node (ref "AXDRS453-LCC_Z-DIR") (pin "2") (pinfunction "AVDD_2") (pintype "passive"))
      (node (ref "C19") (pin "2") (pinfunction "2_2") (pintype "passive"))
    )
    (net (code "38") (name "Net-(AXDRS453-LCC_Z-DIR-CP5)") (class "Default")
      (node (ref "AXDRS453-LCC_Z-DIR") (pin "6") (pinfunction "CP5_6") (pintype "passive"))
      (node (ref "C9") (pin "2") (pinfunction "2_2") (pintype "passive"))
      (node (ref "D1") (pin "K") (pinfunction "C_K") (pintype "passive"))
    )
    (net (code "39") (name "Net-(AXDRS453-LCC_Z-DIR-DVDD)") (class "Default")
      (node (ref "AXDRS453-LCC_Z-DIR") (pin "4") (pinfunction "DVDD_4") (pintype "passive"))
      (node (ref "C12") (pin "2") (pinfunction "2_2") (pintype "passive"))
    )
    (net (code "40") (name "Net-(AXDRS453-LCC_Z-DIR-VX)") (class "Default")
      (node (ref "AXDRS453-LCC_Z-DIR") (pin "9") (pinfunction "VX_9") (pintype "passive"))
      (node (ref "D1") (pin "A") (pinfunction "A_A") (pintype "passive"))
      (node (ref "L1") (pin "2") (pinfunction "2_2") (pintype "passive"))
    )
    (net (code "41") (name "Net-(C5-Pad1)") (class "Default")
      (node (ref "C5") (pin "1") (pinfunction "1_1") (pintype "passive"))
      (node (ref "Y-DIR") (pin "1") (pinfunction "1_1") (pintype "passive"))
    )
    (net (code "42") (name "Net-(C7-Pad1)") (class "Default")
      (node (ref "C7") (pin "1") (pinfunction "1_1") (pintype "passive"))
      (node (ref "Y-DIR") (pin "14") (pinfunction "14_14") (pintype "passive"))
    )
    (net (code "43") (name "Net-(C26-Pad2)") (class "Default")
      (node (ref "C26") (pin "2") (pinfunction "2_2") (pintype "passive"))
      (node (ref "D11") (pin "A") (pinfunction "A_A") (pintype "passive"))
      (node (ref "D12") (pin "A") (pinfunction "A_A") (pintype "passive"))
      (node (ref "D13") (pin "A") (pinfunction "A_A") (pintype "passive"))
      (node (ref "D14") (pin "A") (pinfunction "A_A") (pintype "passive"))
      (node (ref "D15") (pin "A") (pinfunction "A_A") (pintype "passive"))
      (node (ref "D2") (pin "A") (pinfunction "A_A") (pintype "passive"))
      (node (ref "R5") (pin "2") (pinfunction "2_2") (pintype "passive"))
    )
    (net (code "44") (name "Net-(D2-C)") (class "Default")
      (node (ref "D2") (pin "K") (pinfunction "C_K") (pintype "passive"))
      (node (ref "PHOTO") (pin "1") (pinfunction "1_1") (pintype "passive"))
    )
    (net (code "45") (name "Net-(D5-C)") (class "Default")
      (node (ref "C8") (pin "1") (pinfunction "1_1") (pintype "passive"))
      (node (ref "D5") (pin "K") (pinfunction "C_K") (pintype "passive"))
      (node (ref "Y-DIR") (pin "9") (pinfunction "9_9") (pintype "passive"))
    )
    (net (code "46") (name "Net-(D5-PadA)") (class "Default")
      (node (ref "D5") (pin "A") (pinfunction "A_A") (pintype "passive"))
      (node (ref "L2") (pin "2") (pinfunction "2_2") (pintype "passive"))
      (node (ref "Y-DIR") (pin "8") (pinfunction "8_8") (pintype "passive"))
    )
    (net (code "47") (name "Net-(D11-C)") (class "Default")
      (node (ref "D11") (pin "K") (pinfunction "C_K") (pintype "passive"))
      (node (ref "PHOTO") (pin "3") (pinfunction "3_3") (pintype "passive"))
    )
    (net (code "48") (name "Net-(D12-C)") (class "Default")
      (node (ref "D12") (pin "K") (pinfunction "C_K") (pintype "passive"))
      (node (ref "PHOTO") (pin "5") (pinfunction "5_5") (pintype "passive"))
    )
    (net (code "49") (name "Net-(D13-C)") (class "Default")
      (node (ref "D13") (pin "K") (pinfunction "C_K") (pintype "passive"))
      (node (ref "PHOTO") (pin "7") (pinfunction "7_7") (pintype "passive"))
    )
    (net (code "50") (name "Net-(D14-C)") (class "Default")
      (node (ref "D14") (pin "K") (pinfunction "C_K") (pintype "passive"))
      (node (ref "PHOTO") (pin "9") (pinfunction "9_9") (pintype "passive"))
    )
    (net (code "51") (name "Net-(D15-C)") (class "Default")
      (node (ref "D15") (pin "K") (pinfunction "C_K") (pintype "passive"))
      (node (ref "PHOTO") (pin "11") (pinfunction "11_11") (pintype "passive"))
    )
    (net (code "52") (name "Net-(DRIVE-XA-P)") (class "Default")
      (node (ref "DRIVE-XA") (pin "1") (pinfunction "P_1") (pintype "passive"))
      (node (ref "IC3") (pin "2") (pinfunction "OUT1_2") (pintype "output"))
    )
    (net (code "53") (name "Net-(DRIVE-XB-P)") (class "Default")
      (node (ref "DRIVE-XB") (pin "1") (pinfunction "P_1") (pintype "passive"))
      (node (ref "IC3") (pin "6") (pinfunction "OUT2_6") (pintype "output"))
    )
    (net (code "54") (name "Net-(DRIVE-YA-P)") (class "Default")
      (node (ref "DRIVE-YA") (pin "1") (pinfunction "P_1") (pintype "passive"))
      (node (ref "IC4") (pin "2") (pinfunction "OUT1_2") (pintype "output"))
    )
    (net (code "55") (name "Net-(DRIVE-YB-P)") (class "Default")
      (node (ref "DRIVE-YB") (pin "1") (pinfunction "P_1") (pintype "passive"))
      (node (ref "IC4") (pin "6") (pinfunction "OUT2_6") (pintype "output"))
    )
    (net (code "56") (name "Net-(DRIVE-ZA-P)") (class "Default")
      (node (ref "DRIVE-ZA") (pin "1") (pinfunction "P_1") (pintype "passive"))
      (node (ref "IC5") (pin "2") (pinfunction "OUT1_2") (pintype "output"))
    )
    (net (code "57") (name "Net-(DRIVE-ZB-P)") (class "Default")
      (node (ref "DRIVE-ZB") (pin "1") (pinfunction "P_1") (pintype "passive"))
      (node (ref "IC5") (pin "6") (pinfunction "OUT2_6") (pintype "output"))
    )
    (net (code "58") (name "Net-(IC3-FIN)") (class "Default")
      (node (ref "IC3") (pin "3") (pinfunction "FIN_3") (pintype "passive"))
      (node (ref "IC6") (pin "6") (pinfunction "Y0_6") (pintype "output"))
      (node (ref "R14") (pin "1") (pinfunction "1_1") (pintype "passive"))
    )
    (net (code "59") (name "Net-(IC3-RIN)") (class "Default")
      (node (ref "IC3") (pin "5") (pinfunction "RIN_5") (pintype "passive"))
      (node (ref "IC6") (pin "4") (pinfunction "Y1_4") (pintype "output"))
      (node (ref "R15") (pin "1") (pinfunction "1_1") (pintype "passive"))
    )
    (net (code "60") (name "Net-(IC3-VREF)") (class "Default")
      (node (ref "IC3") (pin "1") (pinfunction "VREF_1") (pintype "passive"))
      (node (ref "SJ1") (pin "1") (pinfunction "1_1") (pintype "passive"))
    )
    (net (code "61") (name "Net-(IC4-FIN)") (class "Default")
      (node (ref "IC4") (pin "3") (pinfunction "FIN_3") (pintype "passive"))
      (node (ref "IC7") (pin "6") (pinfunction "Y0_6") (pintype "output"))
      (node (ref "R16") (pin "1") (pinfunction "1_1") (pintype "passive"))
    )
    (net (code "62") (name "Net-(IC4-RIN)") (class "Default")
      (node (ref "IC4") (pin "5") (pinfunction "RIN_5") (pintype "passive"))
      (node (ref "IC7") (pin "4") (pinfunction "Y1_4") (pintype "output"))
      (node (ref "R17") (pin "1") (pinfunction "1_1") (pintype "passive"))
    )
    (net (code "63") (name "Net-(IC4-VREF)") (class "Default")
      (node (ref "IC4") (pin "1") (pinfunction "VREF_1") (pintype "passive"))
      (node (ref "SJ2") (pin "1") (pinfunction "1_1") (pintype "passive"))
    )
    (net (code "64") (name "Net-(IC5-FIN)") (class "Default")
      (node (ref "IC5") (pin "3") (pinfunction "FIN_3") (pintype "passive"))
      (node (ref "IC8") (pin "6") (pinfunction "Y0_6") (pintype "output"))
      (node (ref "R18") (pin "1") (pinfunction "1_1") (pintype "passive"))
    )
    (net (code "65") (name "Net-(IC5-RIN)") (class "Default")
      (node (ref "IC5") (pin "5") (pinfunction "RIN_5") (pintype "passive"))
      (node (ref "IC8") (pin "4") (pinfunction "Y1_4") (pintype "output"))
      (node (ref "R19") (pin "1") (pinfunction "1_1") (pintype "passive"))
    )
    (net (code "66") (name "Net-(IC5-VREF)") (class "Default")
      (node (ref "IC5") (pin "1") (pinfunction "VREF_1") (pintype "passive"))
      (node (ref "SJ3") (pin "1") (pinfunction "1_1") (pintype "passive"))
    )
    (net (code "67") (name "Net-(L4-Pad2)") (class "Default")
      (node (ref "L4") (pin "2") (pinfunction "2_2") (pintype "passive"))
      (node (ref "R1") (pin "1") (pinfunction "1_1") (pintype "passive"))
    )
    (net (code "68") (name "Net-(U$1-ADCVREFN)") (class "Default")
      (node (ref "C3") (pin "1") (pinfunction "1_1") (pintype "passive"))
      (node (ref "U$1") (pin "15") (pinfunction "ADCVREFN_15") (pintype "passive"))
    )
    (net (code "69") (name "Net-(U$1-ADCVREFP)") (class "Default")
      (node (ref "C3") (pin "2") (pinfunction "2_2") (pintype "passive"))
      (node (ref "U$1") (pin "14") (pinfunction "ADCVREFP_14") (pintype "passive"))
    )
    (net (code "70") (name "Net-(U$1-PB30)") (class "Default")
      (node (ref "C16") (pin "2") (pinfunction "2_2") (pintype "passive"))
      (node (ref "CRYSTAL") (pin "P$1") (pinfunction "P$1_P$1") (pintype "passive"))
      (node (ref "U$1") (pin "31") (pinfunction "PB30_31") (pintype "passive"))
    )
    (net (code "71") (name "Net-(U$1-PB31)") (class "Default")
      (node (ref "C17") (pin "2") (pinfunction "2_2") (pintype "passive"))
      (node (ref "CRYSTAL") (pin "P$2") (pinfunction "P$2_P$2") (pintype "passive"))
      (node (ref "U$1") (pin "32") (pinfunction "PB31_32") (pintype "passive"))
    )
    (net (code "72") (name "Net-(U$1-VDDANA)") (class "Default")
      (node (ref "C30") (pin "2") (pinfunction "2_2") (pintype "passive"))
      (node (ref "L4") (pin "1") (pinfunction "1_1") (pintype "passive"))
      (node (ref "U$1") (pin "18") (pinfunction "VDDANA_18") (pintype "passive"))
    )
    (net (code "73") (name "Net-(U$1-VDDCORE)") (class "Default")
      (node (ref "C1") (pin "2") (pinfunction "2_2") (pintype "passive"))
      (node (ref "C2") (pin "2") (pinfunction "2_2") (pintype "passive"))
      (node (ref "U$1") (pin "29") (pinfunction "VDDCORE_29") (pintype "passive"))
    )
    (net (code "74") (name "Net-(U1-CPOUT)") (class "Default")
      (node (ref "C13") (pin "1") (pinfunction "1_1") (pintype "passive"))
      (node (ref "U1") (pin "20") (pinfunction "CPOUT_20") (pintype "passive"))
    )
    (net (code "75") (name "Net-(U1-REGOUT)") (class "Default")
      (node (ref "C14") (pin "1") (pinfunction "1_1") (pintype "passive"))
      (node (ref "U1") (pin "10") (pinfunction "REGOUT_10") (pintype "passive"))
    )
    (net (code "76") (name "Net-(U4-C1)") (class "Default")
      (node (ref "C34") (pin "1") (pinfunction "1_1") (pintype "passive"))
      (node (ref "U4") (pin "10") (pinfunction "C1_10") (pintype "passive"))
    )
    (net (code "77") (name "Net-(U4-SETC)") (class "Default")
      (node (ref "C28") (pin "2") (pinfunction "2_2") (pintype "passive"))
      (node (ref "U4") (pin "12") (pinfunction "SETC_12") (pintype "passive"))
    )
    (net (code "78") (name "Net-(U4-SETP)") (class "Default")
      (node (ref "C28") (pin "1") (pinfunction "1_1") (pintype "passive"))
      (node (ref "U4") (pin "8") (pinfunction "SETP_8") (pintype "passive"))
    )
    (net (code "79") (name "unconnected-(H1-Pad1)") (class "Default")
      (node (ref "H1") (pin "1") (pinfunction "1_1") (pintype "passive"))
    )
    (net (code "80") (name "unconnected-(H1-Pad2)") (class "Default")
      (node (ref "H1") (pin "2") (pinfunction "2_2") (pintype "passive"))
    )
    (net (code "81") (name "unconnected-(H1-Pad3)") (class "Default")
      (node (ref "H1") (pin "3") (pinfunction "3_3") (pintype "passive"))
    )
    (net (code "82") (name "unconnected-(H1-Pad4)") (class "Default")
      (node (ref "H1") (pin "4") (pinfunction "4_4") (pintype "passive"))
    )
    (net (code "83") (name "unconnected-(H1-Pad5)") (class "Default")
      (node (ref "H1") (pin "5") (pinfunction "5_5") (pintype "passive"))
    )
    (net (code "84") (name "unconnected-(H1-Pad6)") (class "Default")
      (node (ref "H1") (pin "6") (pinfunction "6_6") (pintype "passive"))
    )
    (net (code "85") (name "unconnected-(H1-Pad7)") (class "Default")
      (node (ref "H1") (pin "7") (pinfunction "7_7") (pintype "passive"))
    )
    (net (code "86") (name "unconnected-(H1-Pad8)") (class "Default")
      (node (ref "H1") (pin "8") (pinfunction "8_8") (pintype "passive"))
    )
    (net (code "87") (name "unconnected-(H1-Pad9)") (class "Default")
      (node (ref "H1") (pin "9") (pinfunction "9_9") (pintype "passive"))
    )
    (net (code "88") (name "unconnected-(H1-Pad10)") (class "Default")
      (node (ref "H1") (pin "10") (pinfunction "10_10") (pintype "passive"))
    )
    (net (code "89") (name "unconnected-(H1-Pad11)") (class "Default")
      (node (ref "H1") (pin "11") (pinfunction "11_11") (pintype "passive"))
    )
    (net (code "90") (name "unconnected-(H1-Pad13)") (class "Default")
      (node (ref "H1") (pin "13") (pinfunction "13_13") (pintype "passive"))
    )
    (net (code "91") (name "unconnected-(H1-Pad15)") (class "Default")
      (node (ref "H1") (pin "15") (pinfunction "15_15") (pintype "passive"))
    )
    (net (code "92") (name "unconnected-(H1-Pad16)") (class "Default")
      (node (ref "H1") (pin "16") (pinfunction "16_16") (pintype "passive"))
    )
    (net (code "93") (name "unconnected-(H1-Pad17)") (class "Default")
      (node (ref "H1") (pin "17") (pinfunction "17_17") (pintype "passive"))
    )
    (net (code "94") (name "unconnected-(H1-Pad18)") (class "Default")
      (node (ref "H1") (pin "18") (pinfunction "18_18") (pintype "passive"))
    )
    (net (code "95") (name "unconnected-(H1-Pad19)") (class "Default")
      (node (ref "H1") (pin "19") (pinfunction "19_19") (pintype "passive"))
    )
    (net (code "96") (name "unconnected-(H1-Pad20)") (class "Default")
      (node (ref "H1") (pin "20") (pinfunction "20_20") (pintype "passive"))
    )
    (net (code "97") (name "unconnected-(H1-Pad21)") (class "Default")
      (node (ref "H1") (pin "21") (pinfunction "21_21") (pintype "passive"))
    )
    (net (code "98") (name "unconnected-(H1-Pad22)") (class "Default")
      (node (ref "H1") (pin "22") (pinfunction "22_22") (pintype "passive"))
    )
    (net (code "99") (name "unconnected-(H1-Pad23)") (class "Default")
      (node (ref "H1") (pin "23") (pinfunction "23_23") (pintype "passive"))
    )
    (net (code "100") (name "unconnected-(H1-Pad24)") (class "Default")
      (node (ref "H1") (pin "24") (pinfunction "24_24") (pintype "passive"))
    )
    (net (code "101") (name "unconnected-(H1-Pad25)") (class "Default")
      (node (ref "H1") (pin "25") (pinfunction "25_25") (pintype "passive"))
    )
    (net (code "102") (name "unconnected-(H1-Pad26)") (class "Default")
      (node (ref "H1") (pin "26") (pinfunction "26_26") (pintype "passive"))
    )
    (net (code "103") (name "unconnected-(H1-Pad27)") (class "Default")
      (node (ref "H1") (pin "27") (pinfunction "27_27") (pintype "passive"))
    )
    (net (code "104") (name "unconnected-(H1-Pad28)") (class "Default")
      (node (ref "H1") (pin "28") (pinfunction "28_28") (pintype "passive"))
    )
    (net (code "105") (name "unconnected-(H1-Pad29)") (class "Default")
      (node (ref "H1") (pin "29") (pinfunction "29_29") (pintype "passive"))
    )
    (net (code "106") (name "unconnected-(H1-Pad30)") (class "Default")
      (node (ref "H1") (pin "30") (pinfunction "30_30") (pintype "passive"))
    )
    (net (code "107") (name "unconnected-(H1-Pad31)") (class "Default")
      (node (ref "H1") (pin "31") (pinfunction "31_31") (pintype "passive"))
    )
    (net (code "108") (name "unconnected-(H1-Pad32)") (class "Default")
      (node (ref "H1") (pin "32") (pinfunction "32_32") (pintype "passive"))
    )
    (net (code "109") (name "unconnected-(H1-Pad33)") (class "Default")
      (node (ref "H1") (pin "33") (pinfunction "33_33") (pintype "passive"))
    )
    (net (code "110") (name "unconnected-(H1-Pad34)") (class "Default")
      (node (ref "H1") (pin "34") (pinfunction "34_34") (pintype "passive"))
    )
    (net (code "111") (name "unconnected-(H1-Pad35)") (class "Default")
      (node (ref "H1") (pin "35") (pinfunction "35_35") (pintype "passive"))
    )
    (net (code "112") (name "unconnected-(H1-Pad36)") (class "Default")
      (node (ref "H1") (pin "36") (pinfunction "36_36") (pintype "passive"))
    )
    (net (code "113") (name "unconnected-(H1-Pad37)") (class "Default")
      (node (ref "H1") (pin "37") (pinfunction "37_37") (pintype "passive"))
    )
    (net (code "114") (name "unconnected-(H1-Pad38)") (class "Default")
      (node (ref "H1") (pin "38") (pinfunction "38_38") (pintype "passive"))
    )
    (net (code "115") (name "unconnected-(H1-Pad39)") (class "Default")
      (node (ref "H1") (pin "39") (pinfunction "39_39") (pintype "passive"))
    )
    (net (code "116") (name "unconnected-(H1-Pad40)") (class "Default")
      (node (ref "H1") (pin "40") (pinfunction "40_40") (pintype "passive"))
    )
    (net (code "117") (name "unconnected-(H1-Pad41)") (class "Default")
      (node (ref "H1") (pin "41") (pinfunction "41_41") (pintype "passive"))
    )
    (net (code "118") (name "unconnected-(H1-Pad42)") (class "Default")
      (node (ref "H1") (pin "42") (pinfunction "42_42") (pintype "passive"))
    )
    (net (code "119") (name "unconnected-(H1-Pad43)") (class "Default")
      (node (ref "H1") (pin "43") (pinfunction "43_43") (pintype "passive"))
    )
    (net (code "120") (name "unconnected-(H1-Pad44)") (class "Default")
      (node (ref "H1") (pin "44") (pinfunction "44_44") (pintype "passive"))
    )
    (net (code "121") (name "unconnected-(H1-Pad45)") (class "Default")
      (node (ref "H1") (pin "45") (pinfunction "45_45") (pintype "passive"))
    )
    (net (code "122") (name "unconnected-(H1-Pad46)") (class "Default")
      (node (ref "H1") (pin "46") (pinfunction "46_46") (pintype "passive"))
    )
    (net (code "123") (name "unconnected-(H1-Pad47)") (class "Default")
      (node (ref "H1") (pin "47") (pinfunction "47_47") (pintype "passive"))
    )
    (net (code "124") (name "unconnected-(H1-Pad48)") (class "Default")
      (node (ref "H1") (pin "48") (pinfunction "48_48") (pintype "passive"))
    )
    (net (code "125") (name "unconnected-(H1-Pad49)") (class "Default")
      (node (ref "H1") (pin "49") (pinfunction "49_49") (pintype "passive"))
    )
    (net (code "126") (name "unconnected-(H1-Pad50)") (class "Default")
      (node (ref "H1") (pin "50") (pinfunction "50_50") (pintype "passive"))
    )
    (net (code "127") (name "unconnected-(H1-Pad51)") (class "Default")
      (node (ref "H1") (pin "51") (pinfunction "51_51") (pintype "passive"))
    )
    (net (code "128") (name "unconnected-(H1-Pad52)") (class "Default")
      (node (ref "H1") (pin "52") (pinfunction "52_52") (pintype "passive"))
    )
    (net (code "129") (name "unconnected-(H2-Pad1)") (class "Default")
      (node (ref "H2") (pin "1") (pinfunction "1_1") (pintype "passive"))
    )
    (net (code "130") (name "unconnected-(H2-Pad2)") (class "Default")
      (node (ref "H2") (pin "2") (pinfunction "2_2") (pintype "passive"))
    )
    (net (code "131") (name "unconnected-(H2-Pad3)") (class "Default")
      (node (ref "H2") (pin "3") (pinfunction "3_3") (pintype "passive"))
    )
    (net (code "132") (name "unconnected-(H2-Pad4)") (class "Default")
      (node (ref "H2") (pin "4") (pinfunction "4_4") (pintype "passive"))
    )
    (net (code "133") (name "unconnected-(H2-Pad5)") (class "Default")
      (node (ref "H2") (pin "5") (pinfunction "5_5") (pintype "passive"))
    )
    (net (code "134") (name "unconnected-(H2-Pad6)") (class "Default")
      (node (ref "H2") (pin "6") (pinfunction "6_6") (pintype "passive"))
    )
    (net (code "135") (name "unconnected-(H2-Pad7)") (class "Default")
      (node (ref "H2") (pin "7") (pinfunction "7_7") (pintype "passive"))
    )
    (net (code "136") (name "unconnected-(H2-Pad8)") (class "Default")
      (node (ref "H2") (pin "8") (pinfunction "8_8") (pintype "passive"))
    )
    (net (code "137") (name "unconnected-(H2-Pad9)") (class "Default")
      (node (ref "H2") (pin "9") (pinfunction "9_9") (pintype "passive"))
    )
    (net (code "138") (name "unconnected-(H2-Pad10)") (class "Default")
      (node (ref "H2") (pin "10") (pinfunction "10_10") (pintype "passive"))
    )
    (net (code "139") (name "unconnected-(H2-Pad11)") (class "Default")
      (node (ref "H2") (pin "11") (pinfunction "11_11") (pintype "passive"))
    )
    (net (code "140") (name "unconnected-(H2-Pad12)") (class "Default")
      (node (ref "H2") (pin "12") (pinfunction "12_12") (pintype "passive"))
    )
    (net (code "141") (name "unconnected-(H2-Pad13)") (class "Default")
      (node (ref "H2") (pin "13") (pinfunction "13_13") (pintype "passive"))
    )
    (net (code "142") (name "unconnected-(H2-Pad14)") (class "Default")
      (node (ref "H2") (pin "14") (pinfunction "14_14") (pintype "passive"))
    )
    (net (code "143") (name "unconnected-(H2-Pad15)") (class "Default")
      (node (ref "H2") (pin "15") (pinfunction "15_15") (pintype "passive"))
    )
    (net (code "144") (name "unconnected-(H2-Pad16)") (class "Default")
      (node (ref "H2") (pin "16") (pinfunction "16_16") (pintype "passive"))
    )
    (net (code "145") (name "unconnected-(H2-Pad17)") (class "Default")
      (node (ref "H2") (pin "17") (pinfunction "17_17") (pintype "passive"))
    )
    (net (code "146") (name "unconnected-(H2-Pad18)") (class "Default")
      (node (ref "H2") (pin "18") (pinfunction "18_18") (pintype "passive"))
    )
    (net (code "147") (name "unconnected-(H2-Pad19)") (class "Default")
      (node (ref "H2") (pin "19") (pinfunction "19_19") (pintype "passive"))
    )
    (net (code "148") (name "unconnected-(H2-Pad20)") (class "Default")
      (node (ref "H2") (pin "20") (pinfunction "20_20") (pintype "passive"))
    )
    (net (code "149") (name "unconnected-(H2-Pad21)") (class "Default")
      (node (ref "H2") (pin "21") (pinfunction "21_21") (pintype "passive"))
    )
    (net (code "150") (name "unconnected-(H2-Pad22)") (class "Default")
      (node (ref "H2") (pin "22") (pinfunction "22_22") (pintype "passive"))
    )
    (net (code "151") (name "unconnected-(H2-Pad23)") (class "Default")
      (node (ref "H2") (pin "23") (pinfunction "23_23") (pintype "passive"))
    )
    (net (code "152") (name "unconnected-(H2-Pad24)") (class "Default")
      (node (ref "H2") (pin "24") (pinfunction "24_24") (pintype "passive"))
    )
    (net (code "153") (name "unconnected-(H2-Pad31)") (class "Default")
      (node (ref "H2") (pin "31") (pinfunction "31_31") (pintype "passive"))
    )
    (net (code "154") (name "unconnected-(H2-Pad32)") (class "Default")
      (node (ref "H2") (pin "32") (pinfunction "32_32") (pintype "passive"))
    )
    (net (code "155") (name "unconnected-(H2-Pad33)") (class "Default")
      (node (ref "H2") (pin "33") (pinfunction "33_33") (pintype "passive"))
    )
    (net (code "156") (name "unconnected-(H2-Pad34)") (class "Default")
      (node (ref "H2") (pin "34") (pinfunction "34_34") (pintype "passive"))
    )
    (net (code "157") (name "unconnected-(H2-Pad35)") (class "Default")
      (node (ref "H2") (pin "35") (pinfunction "35_35") (pintype "passive"))
    )
    (net (code "158") (name "unconnected-(H2-Pad36)") (class "Default")
      (node (ref "H2") (pin "36") (pinfunction "36_36") (pintype "passive"))
    )
    (net (code "159") (name "unconnected-(H2-Pad37)") (class "Default")
      (node (ref "H2") (pin "37") (pinfunction "37_37") (pintype "passive"))
    )
    (net (code "160") (name "unconnected-(H2-Pad38)") (class "Default")
      (node (ref "H2") (pin "38") (pinfunction "38_38") (pintype "passive"))
    )
    (net (code "161") (name "unconnected-(H2-Pad39)") (class "Default")
      (node (ref "H2") (pin "39") (pinfunction "39_39") (pintype "passive"))
    )
    (net (code "162") (name "unconnected-(H2-Pad40)") (class "Default")
      (node (ref "H2") (pin "40") (pinfunction "40_40") (pintype "passive"))
    )
    (net (code "163") (name "unconnected-(H2-Pad41)") (class "Default")
      (node (ref "H2") (pin "41") (pinfunction "41_41") (pintype "passive"))
    )
    (net (code "164") (name "unconnected-(H2-Pad42)") (class "Default")
      (node (ref "H2") (pin "42") (pinfunction "42_42") (pintype "passive"))
    )
    (net (code "165") (name "unconnected-(H2-Pad43)") (class "Default")
      (node (ref "H2") (pin "43") (pinfunction "43_43") (pintype "passive"))
    )
    (net (code "166") (name "unconnected-(H2-Pad44)") (class "Default")
      (node (ref "H2") (pin "44") (pinfunction "44_44") (pintype "passive"))
    )
    (net (code "167") (name "unconnected-(H2-Pad45)") (class "Default")
      (node (ref "H2") (pin "45") (pinfunction "45_45") (pintype "passive"))
    )
    (net (code "168") (name "unconnected-(H2-Pad46)") (class "Default")
      (node (ref "H2") (pin "46") (pinfunction "46_46") (pintype "passive"))
    )
    (net (code "169") (name "unconnected-(H2-Pad47)") (class "Default")
      (node (ref "H2") (pin "47") (pinfunction "47_47") (pintype "passive"))
    )
    (net (code "170") (name "unconnected-(H2-Pad48)") (class "Default")
      (node (ref "H2") (pin "48") (pinfunction "48_48") (pintype "passive"))
    )
    (net (code "171") (name "unconnected-(H2-Pad49)") (class "Default")
      (node (ref "H2") (pin "49") (pinfunction "49_49") (pintype "passive"))
    )
    (net (code "172") (name "unconnected-(H2-Pad50)") (class "Default")
      (node (ref "H2") (pin "50") (pinfunction "50_50") (pintype "passive"))
    )
    (net (code "173") (name "unconnected-(H2-Pad51)") (class "Default")
      (node (ref "H2") (pin "51") (pinfunction "51_51") (pintype "passive"))
    )
    (net (code "174") (name "unconnected-(H2-Pad52)") (class "Default")
      (node (ref "H2") (pin "52") (pinfunction "52_52") (pintype "passive"))
    )
    (net (code "175") (name "unconnected-(JTAG-Pad3)") (class "Default")
      (node (ref "JTAG") (pin "3") (pinfunction "3_3") (pintype "passive"))
    )
    (net (code "176") (name "unconnected-(JTAG-Pad4)") (class "Default")
      (node (ref "JTAG") (pin "4") (pinfunction "4_4") (pintype "passive"))
    )
    (net (code "177") (name "unconnected-(U$1-DM-Pad24)") (class "Default")
      (node (ref "U$1") (pin "24") (pinfunction "DM_24") (pintype "passive"))
    )
    (net (code "178") (name "unconnected-(U$1-DP-Pad25)") (class "Default")
      (node (ref "U$1") (pin "25") (pinfunction "DP_25") (pintype "passive"))
    )
    (net (code "179") (name "unconnected-(U$1-PA20-Pad19)") (class "Default")
      (node (ref "U$1") (pin "19") (pinfunction "PA20_19") (pintype "passive"))
    )
    (net (code "180") (name "unconnected-(U$1-PA21-Pad20)") (class "Default")
      (node (ref "U$1") (pin "20") (pinfunction "PA21_20") (pintype "passive"))
    )
    (net (code "181") (name "unconnected-(U$1-PA22-Pad21)") (class "Default")
      (node (ref "U$1") (pin "21") (pinfunction "PA22_21") (pintype "passive"))
    )
    (net (code "182") (name "unconnected-(U$1-PA23-Pad22)") (class "Default")
      (node (ref "U$1") (pin "22") (pinfunction "PA23_22") (pintype "passive"))
    )
    (net (code "183") (name "unconnected-(U$1-PB01-Pad63)") (class "Default")
      (node (ref "U$1") (pin "63") (pinfunction "PB01_63") (pintype "passive"))
    )
    (net (code "184") (name "unconnected-(U$1-PC02-Pad33)") (class "Default")
      (node (ref "U$1") (pin "33") (pinfunction "PC02_33") (pintype "passive"))
    )
    (net (code "185") (name "unconnected-(U$1-PC03-Pad34)") (class "Default")
      (node (ref "U$1") (pin "34") (pinfunction "PC03_34") (pintype "passive"))
    )
    (net (code "186") (name "unconnected-(U$1-PD13-Pad55)") (class "Default")
      (node (ref "U$1") (pin "55") (pinfunction "PD13_55") (pintype "passive"))
    )
    (net (code "187") (name "unconnected-(U$1-PD14-Pad56)") (class "Default")
      (node (ref "U$1") (pin "56") (pinfunction "PD14_56") (pintype "passive"))
    )
    (net (code "188") (name "unconnected-(U$1-PD21-Pad57)") (class "Default")
      (node (ref "U$1") (pin "57") (pinfunction "PD21_57") (pintype "passive"))
    )
    (net (code "189") (name "unconnected-(U$1-PD30-Pad61)") (class "Default")
      (node (ref "U$1") (pin "61") (pinfunction "PD30_61") (pintype "passive"))
    )
    (net (code "190") (name "unconnected-(U$1-VBUS-Pad23)") (class "Default")
      (node (ref "U$1") (pin "23") (pinfunction "VBUS_23") (pintype "passive"))
    )
    (net (code "191") (name "unconnected-(U1-INT-Pad12)") (class "Default")
      (node (ref "U1") (pin "12") (pinfunction "INT_12") (pintype "passive"))
    )
    (net (code "192") (name "unconnected-(U2-INT1-Pad8)") (class "Default")
      (node (ref "U2") (pin "8") (pinfunction "INT1_8") (pintype "passive"))
    )
    (net (code "193") (name "unconnected-(U2-INT2-Pad9)") (class "Default")
      (node (ref "U2") (pin "9") (pinfunction "INT2_9") (pintype "passive"))
    )
    (net (code "194") (name "unconnected-(U2-NC-Pad3)") (class "Default")
      (node (ref "U2") (pin "3") (pinfunction "NC_3") (pintype "passive"))
    )
    (net (code "195") (name "unconnected-(U2-NC-Pad10)") (class "Default")
      (node (ref "U2") (pin "10") (pinfunction "NC_10") (pintype "passive"))
    )
    (net (code "196") (name "unconnected-(U2-NC-Pad11)") (class "Default")
      (node (ref "U2") (pin "11") (pinfunction "NC_11") (pintype "passive"))
    )
    (net (code "197") (name "unconnected-(U4-NC-Pad3)") (class "Default")
      (node (ref "U4") (pin "3") (pinfunction "NC_3") (pintype "passive"))
    )
    (net (code "198") (name "unconnected-(U4-NC-Pad5)") (class "Default")
      (node (ref "U4") (pin "5") (pinfunction "NC_5") (pintype "passive"))
    )
    (net (code "199") (name "unconnected-(U4-NC-Pad6)") (class "Default")
      (node (ref "U4") (pin "6") (pinfunction "NC_6") (pintype "passive"))
    )
    (net (code "200") (name "unconnected-(U4-NC-Pad7)") (class "Default")
      (node (ref "U4") (pin "7") (pinfunction "NC_7") (pintype "passive"))
    )
    (net (code "201") (name "unconnected-(U4-NC-Pad14)") (class "Default")
      (node (ref "U4") (pin "14") (pinfunction "NC_14") (pintype "passive"))
    )
  )
)
